# UsbOLED.net
KiCad netlist of a schematic drawn in EAGLE
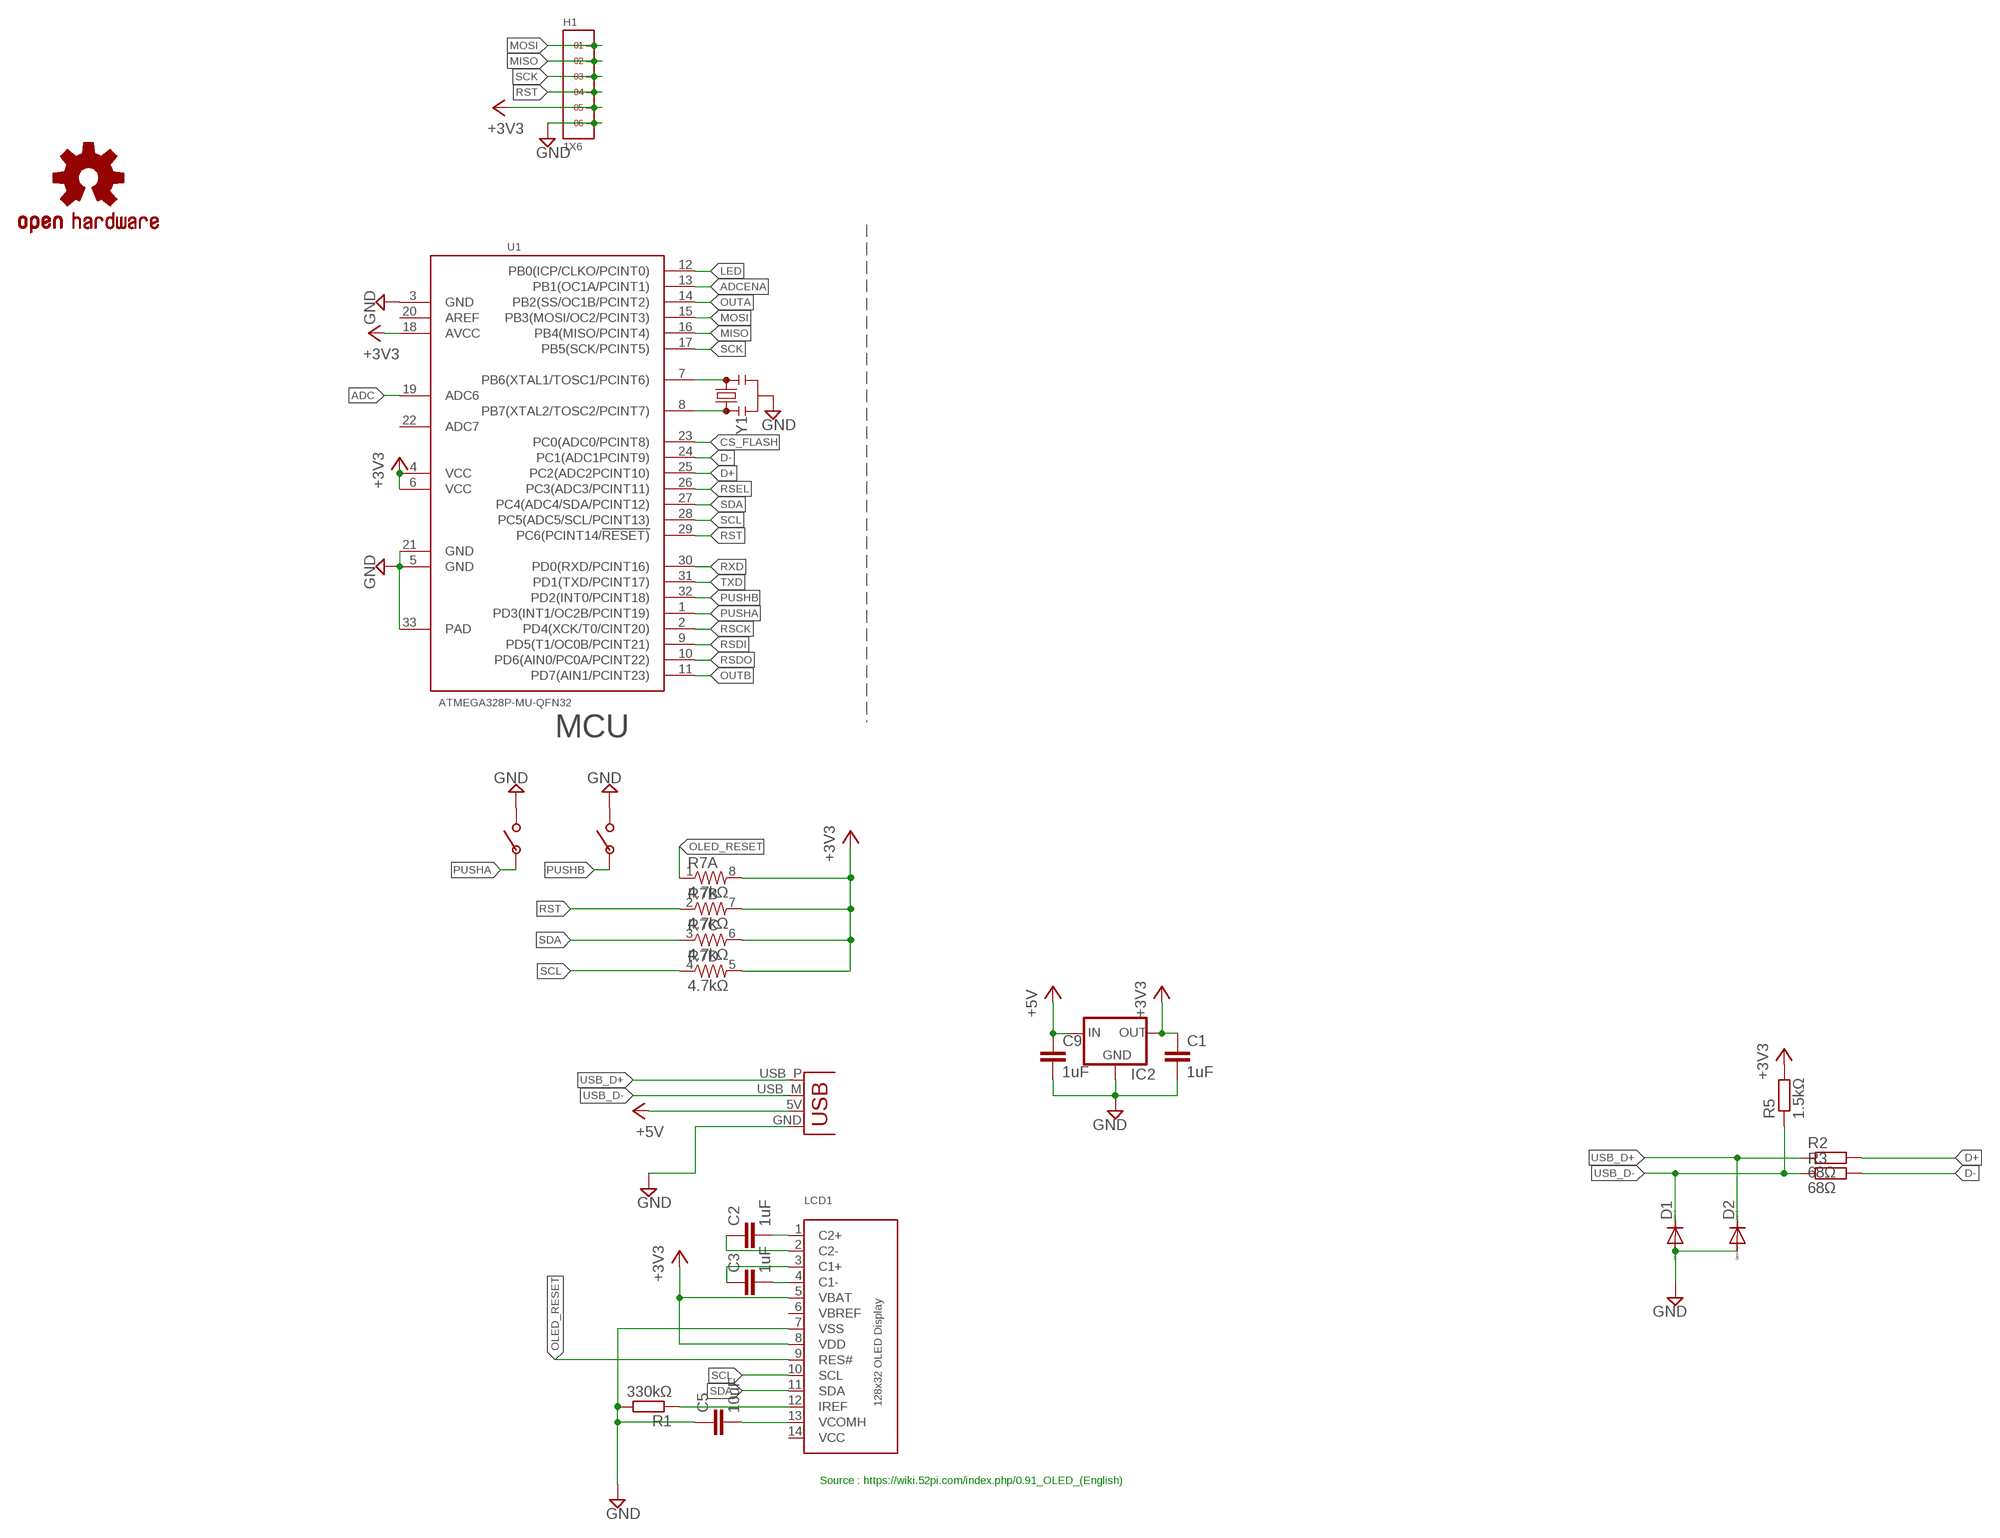
[diagram p0: schematic, sheet 1]

(export (version "E")
  (design (tool "Eeschema 10.0.6"))
  (components
    (comp (ref "C1")
      (value "1uF")
      (footprint "eagle-import:C0603")
      (libsource (lib "eagle-import") (part "C-EUC0603"))
    )
    (comp (ref "C2")
      (value "1uF")
      (footprint "eagle-import:C0603")
      (libsource (lib "eagle-import") (part "C-EUC0603"))
    )
    (comp (ref "C3")
      (value "1uF")
      (footprint "eagle-import:C0603")
      (libsource (lib "eagle-import") (part "C-EUC0603"))
    )
    (comp (ref "C5")
      (value "10uF")
      (footprint "eagle-import:C0603")
      (libsource (lib "eagle-import") (part "C-EUC0603"))
    )
    (comp (ref "C9")
      (value "1uF")
      (footprint "eagle-import:C0603")
      (libsource (lib "eagle-import") (part "C-EUC0603"))
    )
    (comp (ref "D1")
      (value "DIODE-SOD523")
      (footprint "eagle-import:SOD523")
      (libsource (lib "eagle-import") (part "DIODE-SOD523"))
    )
    (comp (ref "D2")
      (value "DIODE-SOD523")
      (footprint "eagle-import:SOD523")
      (libsource (lib "eagle-import") (part "DIODE-SOD523"))
    )
    (comp (ref "H1")
      (value "1X6")
      (footprint "eagle-import:1X6")
      (libsource (lib "eagle-import") (part "1X6"))
    )
    (comp (ref "IC2")
      (value "MCP1700TT")
      (footprint "eagle-import:SOT-23")
      (libsource (lib "eagle-import") (part "MCP1700TT"))
    )
    (comp (ref "LCD1")
      (value "DISP_OLED_UG-2832HSWEG02")
      (footprint "eagle-import:UG-2832HSWEG02_WRAPUNDER")
      (libsource (lib "eagle-import") (part "DISP_OLED_UG-2832HSWEG02"))
    )
    (comp (ref "LOGO1")
      (value "OSHW-LOGOS")
      (footprint "eagle-import:OSHW-LOGO-S")
      (libsource (lib "eagle-import") (part "OSHW-LOGOS"))
    )
    (comp (ref "R1")
      (value "330kΩ")
      (footprint "eagle-import:R0603")
      (libsource (lib "eagle-import") (part "R-EU_R0603"))
    )
    (comp (ref "R2")
      (value "68Ω")
      (footprint "eagle-import:R0603")
      (libsource (lib "eagle-import") (part "R-EU_R0603"))
    )
    (comp (ref "R3")
      (value "68Ω")
      (footprint "eagle-import:R0603")
      (libsource (lib "eagle-import") (part "R-EU_R0603"))
    )
    (comp (ref "R5")
      (value "1.5kΩ")
      (footprint "eagle-import:R0603")
      (libsource (lib "eagle-import") (part "R-EU_R0603"))
    )
    (comp (ref "R7")
      (value "4.7kΩ")
      (footprint "eagle-import:0603-ARV")
      (libsource (lib "eagle-import") (part "RESISTOR-ARRAY0603-ARV"))
    )
    (comp (ref "U$1")
      (value "PUSHBUTTON_4X2.5")
      (footprint "eagle-import:PUSHBUTTON_4X2.5")
      (libsource (lib "eagle-import") (part "PUSHBUTTON_4X2.5"))
    )
    (comp (ref "U$3")
      (value "PUSHBUTTON_4X2.5")
      (footprint "eagle-import:PUSHBUTTON_4X2.5")
      (libsource (lib "eagle-import") (part "PUSHBUTTON_4X2.5"))
    )
    (comp (ref "U1")
      (value "ATMEGA328P-MU-QFN32")
      (footprint "eagle-import:QFN32G-0.5-5X5MM")
      (fields (field (name "MPN") "ATMEGA328P-MU"))
      (libsource (lib "eagle-import") (part "MCU-ATMEGA328P-MU(QFN32)"))
    )
    (comp (ref "X1")
      (value "USBPCB")
      (footprint "eagle-import:USB-A-PCB")
      (libsource (lib "eagle-import") (part "USBPCB"))
    )
    (comp (ref "Y1")
      (value "RESONATORSMD-3.2X1.3")
      (footprint "eagle-import:RESONATOR-SMD-3.2X1.3")
      (libsource (lib "eagle-import") (part "RESONATORSMD-3.2X1.3"))
    )
  )
  (nets
    (net (code "1") (name "+3V3") (class "Default")
      (node (ref "C1") (pin "1") (pinfunction "1_1") (pintype "passive"))
      (node (ref "H1") (pin "5") (pinfunction "5_5") (pintype "bidirectional"))
      (node (ref "IC2") (pin "2") (pinfunction "OUT_2") (pintype "passive"))
      (node (ref "LCD1") (pin "5") (pinfunction "VBAT_5") (pintype "power_in"))
      (node (ref "LCD1") (pin "8") (pinfunction "VDD_8") (pintype "power_in"))
      (node (ref "R5") (pin "2") (pinfunction "2_2") (pintype "passive"))
      (node (ref "R7") (pin "5") (pinfunction "2_5") (pintype "passive"))
      (node (ref "R7") (pin "6") (pinfunction "2_6") (pintype "passive"))
      (node (ref "R7") (pin "7") (pinfunction "2_7") (pintype "passive"))
      (node (ref "R7") (pin "8") (pinfunction "2_8") (pintype "passive"))
      (node (ref "U1") (pin "18") (pinfunction "AVCC_18") (pintype "bidirectional"))
      (node (ref "U1") (pin "4") (pinfunction "VCC_4") (pintype "bidirectional"))
      (node (ref "U1") (pin "6") (pinfunction "VCC_6") (pintype "bidirectional"))
    )
    (net (code "2") (name "+5V") (class "Default")
      (node (ref "C9") (pin "1") (pinfunction "1_1") (pintype "passive"))
      (node (ref "IC2") (pin "3") (pinfunction "IN_3") (pintype "input"))
      (node (ref "X1") (pin "5V") (pinfunction "VBUS_5V") (pintype "bidirectional"))
    )
    (net (code "3") (name "/VBREF") (class "Default")
      (node (ref "LCD1") (pin "6") (pinfunction "VBREF_6") (pintype "power_in"))
    )
    (net (code "4") (name "/VCC") (class "Default")
      (node (ref "LCD1") (pin "14") (pinfunction "VCC_14") (pintype "power_in"))
    )
    (net (code "5") (name "ADC") (class "Default")
      (node (ref "U1") (pin "19") (pinfunction "ADC6_19") (pintype "bidirectional"))
    )
    (net (code "6") (name "ADCENA") (class "Default")
      (node (ref "U1") (pin "13") (pinfunction "PB1(OC1A/PCINT1)_13") (pintype "bidirectional"))
    )
    (net (code "7") (name "CS_FLASH") (class "Default")
      (node (ref "U1") (pin "23") (pinfunction "PC0(ADC0/PCINT8)_23") (pintype "bidirectional"))
    )
    (net (code "8") (name "D+") (class "Default")
      (node (ref "R2") (pin "2") (pinfunction "2_2") (pintype "passive"))
      (node (ref "U1") (pin "25") (pinfunction "PC2(ADC2PCINT10)_25") (pintype "bidirectional"))
    )
    (net (code "9") (name "D-") (class "Default")
      (node (ref "R3") (pin "2") (pinfunction "2_2") (pintype "passive"))
      (node (ref "U1") (pin "24") (pinfunction "PC1(ADC1PCINT9)_24") (pintype "bidirectional"))
    )
    (net (code "10") (name "GND") (class "Default")
      (node (ref "C1") (pin "2") (pinfunction "2_2") (pintype "passive"))
      (node (ref "C5") (pin "1") (pinfunction "1_1") (pintype "passive"))
      (node (ref "C9") (pin "2") (pinfunction "2_2") (pintype "passive"))
      (node (ref "D1") (pin "A") (pinfunction "A_A") (pintype "passive"))
      (node (ref "D2") (pin "A") (pinfunction "A_A") (pintype "passive"))
      (node (ref "H1") (pin "6") (pinfunction "6_6") (pintype "bidirectional"))
      (node (ref "IC2") (pin "1") (pinfunction "GND_1") (pintype "input"))
      (node (ref "LCD1") (pin "7") (pinfunction "VSS_7") (pintype "power_in"))
      (node (ref "R1") (pin "2") (pinfunction "2_2") (pintype "passive"))
      (node (ref "U$1") (pin "P$2") (pinfunction "P$2_P$2") (pintype "bidirectional"))
      (node (ref "U$3") (pin "P$2") (pinfunction "P$2_P$2") (pintype "bidirectional"))
      (node (ref "U1") (pin "21") (pinfunction "GND_21") (pintype "bidirectional"))
      (node (ref "U1") (pin "3") (pinfunction "GND_3") (pintype "bidirectional"))
      (node (ref "U1") (pin "33") (pinfunction "PAD_33") (pintype "bidirectional"))
      (node (ref "U1") (pin "5") (pinfunction "GND_5") (pintype "bidirectional"))
      (node (ref "X1") (pin "GND") (pinfunction "GND_GND") (pintype "bidirectional"))
      (node (ref "Y1") (pin "2") (pinfunction "2_2") (pintype "passive"))
    )
    (net (code "11") (name "LED") (class "Default")
      (node (ref "U1") (pin "12") (pinfunction "PB0(ICP/CLKO/PCINT0)_12") (pintype "bidirectional"))
    )
    (net (code "12") (name "MISO") (class "Default")
      (node (ref "H1") (pin "2") (pinfunction "2_2") (pintype "bidirectional"))
      (node (ref "U1") (pin "16") (pinfunction "PB4(MISO/PCINT4)_16") (pintype "bidirectional"))
    )
    (net (code "13") (name "MOSI") (class "Default")
      (node (ref "H1") (pin "1") (pinfunction "1_1") (pintype "bidirectional"))
      (node (ref "U1") (pin "15") (pinfunction "PB3(MOSI/OC2/PCINT3)_15") (pintype "bidirectional"))
    )
    (net (code "14") (name "Net-(LCD1-C1+)") (class "Default")
      (node (ref "C3") (pin "1") (pinfunction "1_1") (pintype "passive"))
      (node (ref "LCD1") (pin "3") (pinfunction "C1+_3") (pintype "bidirectional"))
    )
    (net (code "15") (name "Net-(LCD1-C1-)") (class "Default")
      (node (ref "C3") (pin "2") (pinfunction "2_2") (pintype "passive"))
      (node (ref "LCD1") (pin "4") (pinfunction "C1-_4") (pintype "bidirectional"))
    )
    (net (code "16") (name "Net-(LCD1-C2+)") (class "Default")
      (node (ref "C2") (pin "2") (pinfunction "2_2") (pintype "passive"))
      (node (ref "LCD1") (pin "1") (pinfunction "C2+_1") (pintype "bidirectional"))
    )
    (net (code "17") (name "Net-(LCD1-C2-)") (class "Default")
      (node (ref "C2") (pin "1") (pinfunction "1_1") (pintype "passive"))
      (node (ref "LCD1") (pin "2") (pinfunction "C2-_2") (pintype "bidirectional"))
    )
    (net (code "18") (name "Net-(LCD1-IREF)") (class "Default")
      (node (ref "LCD1") (pin "12") (pinfunction "IREF_12") (pintype "bidirectional"))
      (node (ref "R1") (pin "1") (pinfunction "1_1") (pintype "passive"))
    )
    (net (code "19") (name "Net-(LCD1-VCOMH)") (class "Default")
      (node (ref "C5") (pin "2") (pinfunction "2_2") (pintype "passive"))
      (node (ref "LCD1") (pin "13") (pinfunction "VCOMH_13") (pintype "power_in"))
    )
    (net (code "20") (name "Net-(U1-PB6(XTAL1{slash}TOSC1{slash}PCINT6))") (class "Default")
      (node (ref "U1") (pin "7") (pinfunction "PB6(XTAL1/TOSC1/PCINT6)_7") (pintype "bidirectional"))
      (node (ref "Y1") (pin "3") (pinfunction "3_3") (pintype "passive"))
    )
    (net (code "21") (name "Net-(U1-PB7(XTAL2{slash}TOSC2{slash}PCINT7))") (class "Default")
      (node (ref "U1") (pin "8") (pinfunction "PB7(XTAL2/TOSC2/PCINT7)_8") (pintype "bidirectional"))
      (node (ref "Y1") (pin "1") (pinfunction "1_1") (pintype "passive"))
    )
    (net (code "22") (name "OLED_RESET") (class "Default")
      (node (ref "LCD1") (pin "9") (pinfunction "RES#_9") (pintype "bidirectional"))
      (node (ref "R7") (pin "1") (pinfunction "1_1") (pintype "passive"))
    )
    (net (code "23") (name "OUTA") (class "Default")
      (node (ref "U1") (pin "14") (pinfunction "PB2(SS/OC1B/PCINT2)_14") (pintype "bidirectional"))
    )
    (net (code "24") (name "OUTB") (class "Default")
      (node (ref "U1") (pin "11") (pinfunction "PD7(AIN1/PCINT23)_11") (pintype "bidirectional"))
    )
    (net (code "25") (name "PUSHA") (class "Default")
      (node (ref "U$1") (pin "P$1") (pinfunction "P$1_P$1") (pintype "bidirectional"))
      (node (ref "U1") (pin "1") (pinfunction "PD3(INT1/OC2B/PCINT19)_1") (pintype "bidirectional"))
    )
    (net (code "26") (name "PUSHB") (class "Default")
      (node (ref "U$3") (pin "P$1") (pinfunction "P$1_P$1") (pintype "bidirectional"))
      (node (ref "U1") (pin "32") (pinfunction "PD2(INT0/PCINT18)_32") (pintype "bidirectional"))
    )
    (net (code "27") (name "RSCK") (class "Default")
      (node (ref "U1") (pin "2") (pinfunction "PD4(XCK/T0/CINT20)_2") (pintype "bidirectional"))
    )
    (net (code "28") (name "RSDI") (class "Default")
      (node (ref "U1") (pin "9") (pinfunction "PD5(T1/OC0B/PCINT21)_9") (pintype "bidirectional"))
    )
    (net (code "29") (name "RSDO") (class "Default")
      (node (ref "U1") (pin "10") (pinfunction "PD6(AIN0/PC0A/PCINT22)_10") (pintype "bidirectional"))
    )
    (net (code "30") (name "RSEL") (class "Default")
      (node (ref "U1") (pin "26") (pinfunction "PC3(ADC3/PCINT11)_26") (pintype "bidirectional"))
    )
    (net (code "31") (name "RST") (class "Default")
      (node (ref "H1") (pin "4") (pinfunction "4_4") (pintype "bidirectional"))
      (node (ref "R7") (pin "2") (pinfunction "1_2") (pintype "passive"))
      (node (ref "U1") (pin "29") (pinfunction "PC6(PCINT14/~{RESET})_29") (pintype "bidirectional"))
    )
    (net (code "32") (name "RXD") (class "Default")
      (node (ref "U1") (pin "30") (pinfunction "PD0(RXD/PCINT16)_30") (pintype "bidirectional"))
    )
    (net (code "33") (name "SCK") (class "Default")
      (node (ref "H1") (pin "3") (pinfunction "3_3") (pintype "bidirectional"))
      (node (ref "U1") (pin "17") (pinfunction "PB5(SCK/PCINT5)_17") (pintype "bidirectional"))
    )
    (net (code "34") (name "SCL") (class "Default")
      (node (ref "LCD1") (pin "10") (pinfunction "SCL_10") (pintype "bidirectional"))
      (node (ref "R7") (pin "4") (pinfunction "1_4") (pintype "passive"))
      (node (ref "U1") (pin "28") (pinfunction "PC5(ADC5/SCL/PCINT13)_28") (pintype "bidirectional"))
    )
    (net (code "35") (name "SDA") (class "Default")
      (node (ref "LCD1") (pin "11") (pinfunction "SDA_11") (pintype "bidirectional"))
      (node (ref "R7") (pin "3") (pinfunction "1_3") (pintype "passive"))
      (node (ref "U1") (pin "27") (pinfunction "PC4(ADC4/SDA/PCINT12)_27") (pintype "bidirectional"))
    )
    (net (code "36") (name "TXD") (class "Default")
      (node (ref "U1") (pin "31") (pinfunction "PD1(TXD/PCINT17)_31") (pintype "bidirectional"))
    )
    (net (code "37") (name "USB_D+") (class "Default")
      (node (ref "D2") (pin "C") (pinfunction "C_C") (pintype "passive"))
      (node (ref "R2") (pin "1") (pinfunction "1_1") (pintype "passive"))
      (node (ref "X1") (pin "USB_P") (pinfunction "D+_USB_P") (pintype "bidirectional"))
    )
    (net (code "38") (name "USB_D-") (class "Default")
      (node (ref "D1") (pin "C") (pinfunction "C_C") (pintype "passive"))
      (node (ref "R3") (pin "1") (pinfunction "1_1") (pintype "passive"))
      (node (ref "R5") (pin "1") (pinfunction "1_1") (pintype "passive"))
      (node (ref "X1") (pin "USB_M") (pinfunction "D-_USB_M") (pintype "bidirectional"))
    )
    (net (code "39") (name "unconnected-(U1-ADC7-Pad22)") (class "Default")
      (node (ref "U1") (pin "22") (pinfunction "ADC7_22") (pintype "bidirectional"))
    )
    (net (code "40") (name "unconnected-(U1-AREF-Pad20)") (class "Default")
      (node (ref "U1") (pin "20") (pinfunction "AREF_20") (pintype "bidirectional"))
    )
  )
)
